# latest_schematic.net
KiCad netlist of a schematic drawn in EasyEDA
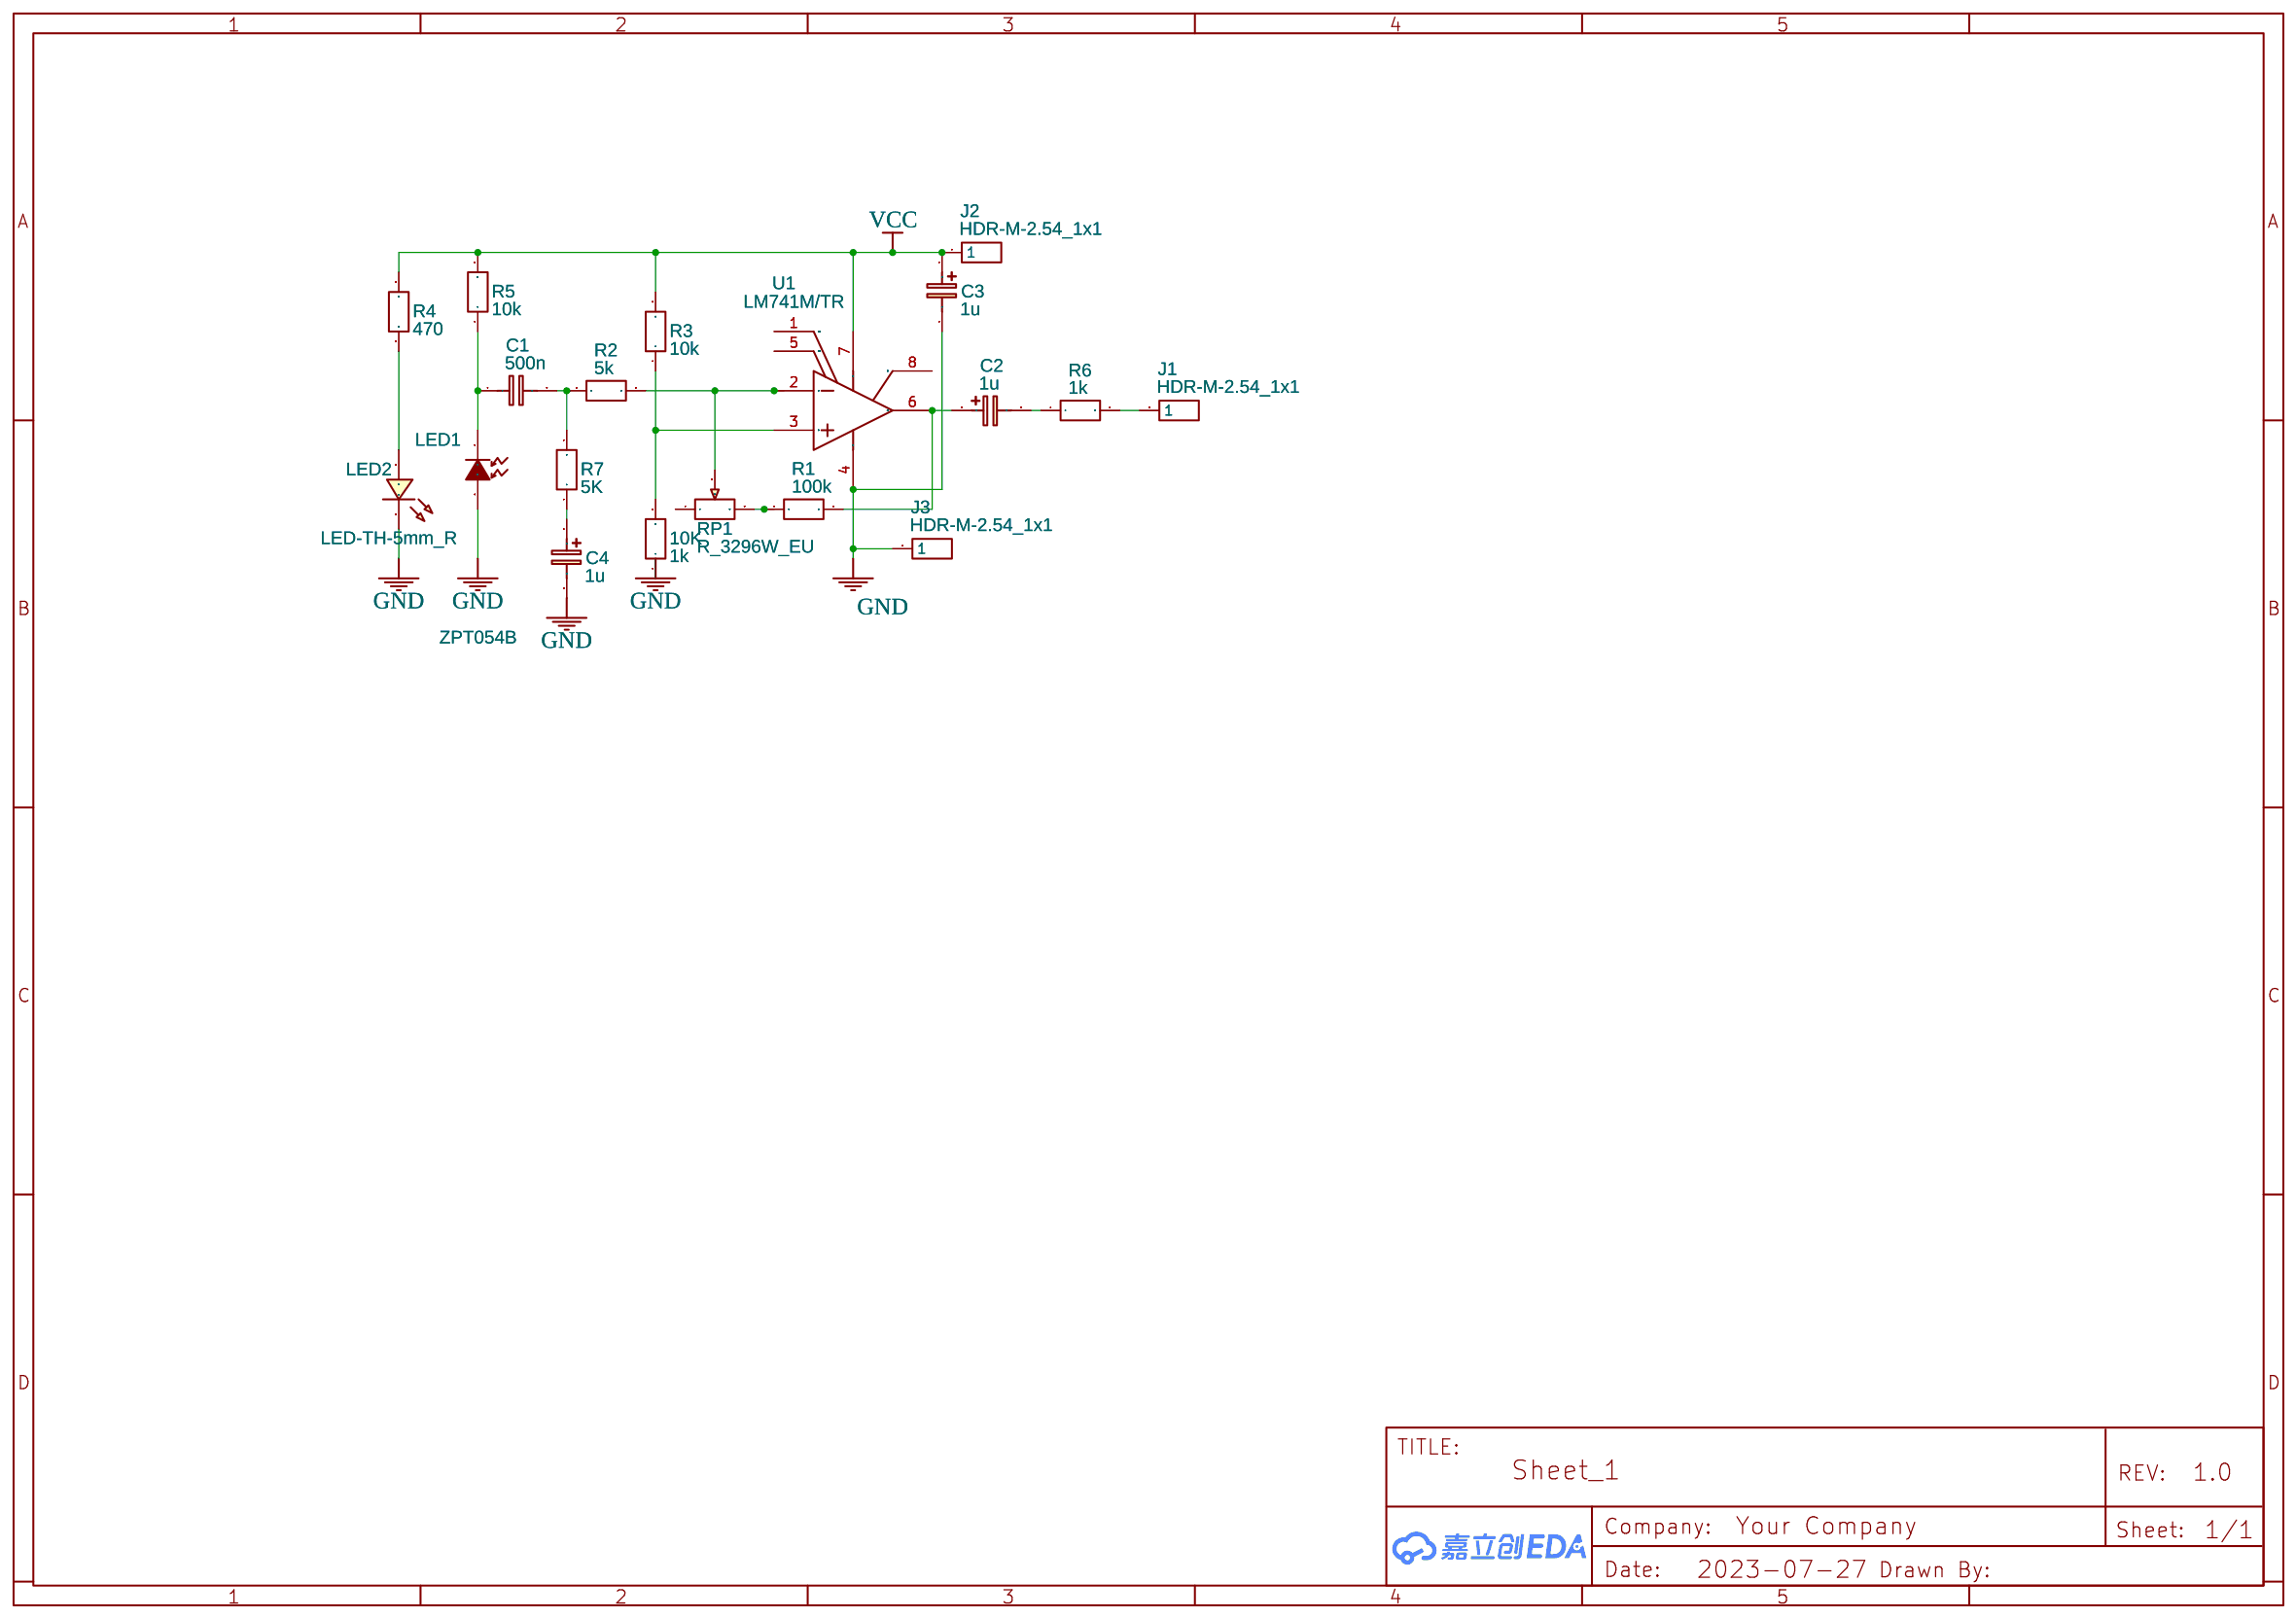
[diagram p0: schematic sheet]

(export (version "E")
  (design (tool "Eeschema 10.0.6"))
  (components
    (comp (ref "10K") (value "1k") (libsource (lib "") (part "R_0603_EU_2")))
    (comp (ref "C1") (value "500n") (libsource (lib "") (part "C_0603_EU")))
    (comp (ref "C2") (value "1u") (libsource (lib "") (part "C_Tan_SMD_A_EU_1")))
    (comp (ref "C3") (value "1u") (libsource (lib "") (part "C_Tan_SMD_A_EU")))
    (comp (ref "C4") (value "1u") (libsource (lib "") (part "C_Tan_SMD_A_EU")))
    (comp (ref "J1")
      (value "HDR-M-2.54_1x1")
      (fields (field (name "BOM_Supplier Part") "C81276"))
      (libsource (lib "") (part "HDR-M-2.54_1x1"))
    )
    (comp (ref "J2")
      (value "HDR-M-2.54_1x1")
      (fields (field (name "BOM_Supplier Part") "C81276"))
      (libsource (lib "") (part "HDR-M-2.54_1x1"))
    )
    (comp (ref "J3")
      (value "HDR-M-2.54_1x1")
      (fields (field (name "BOM_Supplier Part") "C81276"))
      (libsource (lib "") (part "HDR-M-2.54_1x1"))
    )
    (comp (ref "LED1")
      (value "ZPT054B")
      (fields (field (name "Manufacturer") "Chau Light"))
      (libsource (lib "") (part "ZPT054B"))
    )
    (comp (ref "LED2")
      (value "LED-TH-5mm_R")
      (fields
        (field (name "BOM_Manufacturer Part") "333-2SURD/S530-A3")
        (field (name "BOM_Supplier Part") "C87271")
      )
      (libsource (lib "") (part "LED-TH-5mm_R"))
    )
    (comp (ref "R1") (value "100k") (libsource (lib "") (part "R_0603_EU")))
    (comp (ref "R2") (value "5k") (libsource (lib "") (part "R_0603_EU")))
    (comp (ref "R3") (value "10k") (libsource (lib "") (part "R_0603_EU_1")))
    (comp (ref "R4") (value "470") (libsource (lib "") (part "R_0603_EU_1")))
    (comp (ref "R5") (value "10k") (libsource (lib "") (part "R_0603_EU_1")))
    (comp (ref "R6") (value "1k") (libsource (lib "") (part "R_0603_EU")))
    (comp (ref "R7") (value "5K") (libsource (lib "") (part "R_0603_EU_1")))
    (comp (ref "RP1") (value "R_3296W_EU") (libsource (lib "") (part "R_3296W_EU")))
    (comp (ref "U1")
      (value "LM741M/TR")
      (fields (field (name "Manufacturer") "HGSEMI(华冠)"))
      (libsource (lib "") (part "LM741M/TR"))
    )
  )
  (nets
    (net (code "1") (name "GND") (class "Default")
      (node (ref "10K") (pin "1") (pinfunction "1_1") (pintype "unspecified"))
      (node (ref "C3") (pin "2") (pinfunction "2_2") (pintype "unspecified"))
      (node (ref "C4") (pin "2") (pinfunction "2_2") (pintype "unspecified"))
      (node (ref "J3") (pin "1") (pinfunction "1_1") (pintype "input"))
      (node (ref "LED1") (pin "2") (pinfunction "C_2") (pintype "input"))
      (node (ref "LED2") (pin "2") (pinfunction "2_2") (pintype "unspecified"))
      (node (ref "U1") (pin "4") (pinfunction "V-_4") (pintype "passive"))
    )
    (net (code "2") (name "Net-(C1-Pad2)") (class "Default")
      (node (ref "C1") (pin "2") (pinfunction "2_2") (pintype "unspecified"))
      (node (ref "R2") (pin "1") (pinfunction "1_1") (pintype "unspecified"))
      (node (ref "R7") (pin "2") (pinfunction "2_2") (pintype "unspecified"))
    )
    (net (code "3") (name "Net-(C2-Pad2)") (class "Default")
      (node (ref "C2") (pin "2") (pinfunction "2_2") (pintype "unspecified"))
      (node (ref "R6") (pin "1") (pinfunction "1_1") (pintype "unspecified"))
    )
    (net (code "4") (name "Net-(C4-Pad1)") (class "Default")
      (node (ref "C4") (pin "1") (pinfunction "1_1") (pintype "unspecified"))
      (node (ref "R7") (pin "1") (pinfunction "1_1") (pintype "unspecified"))
    )
    (net (code "5") (name "Net-(J1-Pad1)") (class "Default")
      (node (ref "J1") (pin "1") (pinfunction "1_1") (pintype "input"))
      (node (ref "R6") (pin "2") (pinfunction "2_2") (pintype "unspecified"))
    )
    (net (code "6") (name "Net-(LED1-E)") (class "Default")
      (node (ref "C1") (pin "1") (pinfunction "1_1") (pintype "unspecified"))
      (node (ref "LED1") (pin "1") (pinfunction "E_1") (pintype "input"))
      (node (ref "R5") (pin "1") (pinfunction "1_1") (pintype "unspecified"))
    )
    (net (code "7") (name "Net-(LED2-Pad1)") (class "Default")
      (node (ref "LED2") (pin "1") (pinfunction "1_1") (pintype "unspecified"))
      (node (ref "R4") (pin "1") (pinfunction "1_1") (pintype "unspecified"))
    )
    (net (code "8") (name "Net-(R1-Pad1)") (class "Default")
      (node (ref "R1") (pin "1") (pinfunction "1_1") (pintype "unspecified"))
      (node (ref "RP1") (pin "3") (pinfunction "3_3") (pintype "input"))
    )
    (net (code "9") (name "Net-(U1-IN+)") (class "Default")
      (node (ref "10K") (pin "2") (pinfunction "2_2") (pintype "unspecified"))
      (node (ref "R3") (pin "1") (pinfunction "1_1") (pintype "unspecified"))
      (node (ref "U1") (pin "3") (pinfunction "IN+_3") (pintype "unspecified"))
    )
    (net (code "10") (name "Net-(U1-IN-)") (class "Default")
      (node (ref "R2") (pin "2") (pinfunction "2_2") (pintype "unspecified"))
      (node (ref "RP1") (pin "2") (pinfunction "2_2") (pintype "input"))
      (node (ref "U1") (pin "2") (pinfunction "IN-_2") (pintype "unspecified"))
    )
    (net (code "11") (name "Net-(U1-OUT)") (class "Default")
      (node (ref "C2") (pin "1") (pinfunction "1_1") (pintype "unspecified"))
      (node (ref "R1") (pin "2") (pinfunction "2_2") (pintype "unspecified"))
      (node (ref "U1") (pin "6") (pinfunction "OUT_6") (pintype "output"))
    )
    (net (code "12") (name "VCC") (class "Default")
      (node (ref "C3") (pin "1") (pinfunction "1_1") (pintype "unspecified"))
      (node (ref "J2") (pin "1") (pinfunction "1_1") (pintype "input"))
      (node (ref "R3") (pin "2") (pinfunction "2_2") (pintype "unspecified"))
      (node (ref "R4") (pin "2") (pinfunction "2_2") (pintype "unspecified"))
      (node (ref "R5") (pin "2") (pinfunction "2_2") (pintype "unspecified"))
      (node (ref "U1") (pin "7") (pinfunction "V+_7") (pintype "passive"))
    )
    (net (code "13") (name "unconnected-(RP1-Pad1)") (class "Default")
      (node (ref "RP1") (pin "1") (pinfunction "1_1") (pintype "input"))
    )
    (net (code "14") (name "unconnected-(U1-NC-Pad8)") (class "Default")
      (node (ref "U1") (pin "8") (pinfunction "NC_8") (pintype "unspecified"))
    )
    (net (code "15") (name "unconnected-(U1-OFFSET_NULL-Pad1)") (class "Default")
      (node (ref "U1") (pin "1") (pinfunction "OFFSET_NULL_1") (pintype "unspecified"))
    )
    (net (code "16") (name "unconnected-(U1-OFFSET_NULL-Pad5)") (class "Default")
      (node (ref "U1") (pin "5") (pinfunction "OFFSET_NULL_5") (pintype "unspecified"))
    )
  )
)
